# 03_OUTPUT.net
KiCad netlist of a schematic drawn in Altium Designer
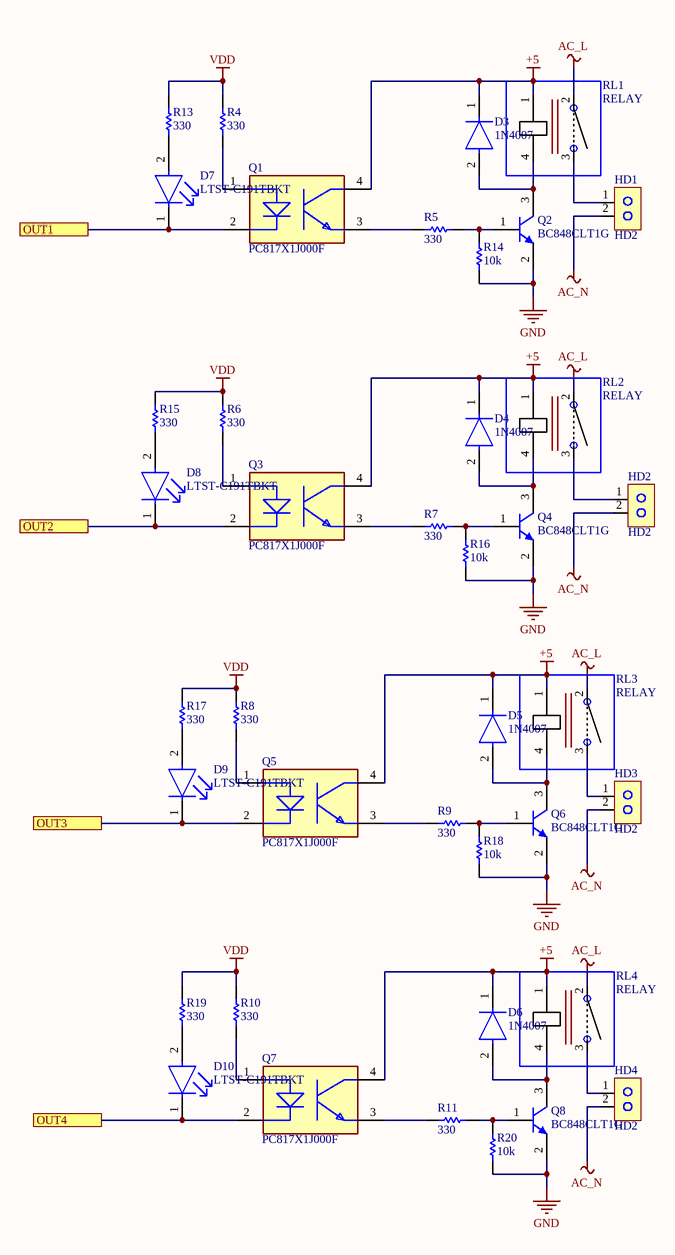
[diagram p0: 03. OUTPUT.SchDoc]

(export (version "E")
  (design (tool "Eeschema 10.0.6"))
  (components
    (comp (ref "D3")
      (value "1N4007")
      (footprint "FP-SMA-MFG")
      (description "DIODE GEN PURP 600V 1A SMA")
      (fields
        (field (name "MANUFACTURER") "STMicroelectronics")
        (field (name "OCTOPART") "https://octopart.com/stth1l06a-stmicroelectronics-324385")
      )
      (libsource (lib "Altium Content Vault") (part "d7152d700b627762746794eb795d46e"))
    )
    (comp (ref "D4")
      (value "1N4007")
      (footprint "FP-SMA-MFG")
      (description "DIODE GEN PURP 600V 1A SMA")
      (fields
        (field (name "MANUFACTURER") "STMicroelectronics")
        (field (name "OCTOPART") "https://octopart.com/stth1l06a-stmicroelectronics-324385")
      )
      (libsource (lib "Altium Content Vault") (part "d7152d700b627762746794eb795d46e"))
    )
    (comp (ref "D5")
      (value "1N4007")
      (footprint "FP-SMA-MFG")
      (description "DIODE GEN PURP 600V 1A SMA")
      (fields
        (field (name "MANUFACTURER") "STMicroelectronics")
        (field (name "OCTOPART") "https://octopart.com/stth1l06a-stmicroelectronics-324385")
      )
      (libsource (lib "Altium Content Vault") (part "d7152d700b627762746794eb795d46e"))
    )
    (comp (ref "D6")
      (value "1N4007")
      (footprint "FP-SMA-MFG")
      (description "DIODE GEN PURP 600V 1A SMA")
      (fields
        (field (name "MANUFACTURER") "STMicroelectronics")
        (field (name "OCTOPART") "https://octopart.com/stth1l06a-stmicroelectronics-324385")
      )
      (libsource (lib "Altium Content Vault") (part "d7152d700b627762746794eb795d46e"))
    )
    (comp (ref "D7")
      (value "LTST-C191TBKT")
      (footprint "FP-LTST-C191TBKT-MFG")
      (description "LED BLUE CLEAR CHIP SMD")
      (libsource (lib "Altium Content Vault") (part "8706943c75ba83719d021d2fdc84c58"))
    )
    (comp (ref "D8")
      (value "LTST-C191TBKT")
      (footprint "FP-LTST-C191TBKT-MFG")
      (description "LED BLUE CLEAR CHIP SMD")
      (libsource (lib "Altium Content Vault") (part "8706943c75ba83719d021d2fdc84c58"))
    )
    (comp (ref "D9")
      (value "LTST-C191TBKT")
      (footprint "FP-LTST-C191TBKT-MFG")
      (description "LED BLUE CLEAR CHIP SMD")
      (libsource (lib "Altium Content Vault") (part "8706943c75ba83719d021d2fdc84c58"))
    )
    (comp (ref "D10")
      (value "LTST-C191TBKT")
      (footprint "FP-LTST-C191TBKT-MFG")
      (description "LED BLUE CLEAR CHIP SMD")
      (libsource (lib "Altium Content Vault") (part "8706943c75ba83719d021d2fdc84c58"))
    )
    (comp (ref "HD1") (value "HD2") (footprint "HD2 5.08mm") (libsource (lib "SyTungNguyen") (part "HD2")))
    (comp (ref "HD2") (value "HD2") (footprint "HD2 5.08mm") (libsource (lib "SyTungNguyen") (part "HD2")))
    (comp (ref "HD3") (value "HD2") (footprint "HD2 5.08mm") (libsource (lib "SyTungNguyen") (part "HD2")))
    (comp (ref "HD4") (value "HD2") (footprint "HD2 5.08mm") (libsource (lib "SyTungNguyen") (part "HD2")))
    (comp (ref "Q1")
      (value "PC817X1J000F")
      (footprint "FP-PC817X1J000F-MFG")
      (description "OPTOISOLATOR 5KV TRANS 4DIP")
      (libsource (lib "Altium Content Vault") (part "8d9d817270a4e8f0d794346117f6aa3"))
    )
    (comp (ref "Q2")
      (value "BC848CLT1G")
      (footprint "SOT23-3")
      (description "General Purpose Transistor, NPN Silicon, 3-Pin SOT-23, Pb-Free, Tape and Reel")
      (fields (field (name "MANUFACTURER") "On Semiconductor"))
      (libsource (lib "SyTungNguyen") (part "ONSC-NPN-B1E2C3-3"))
    )
    (comp (ref "Q3")
      (value "PC817X1J000F")
      (footprint "FP-PC817X1J000F-MFG")
      (description "OPTOISOLATOR 5KV TRANS 4DIP")
      (libsource (lib "Altium Content Vault") (part "8d9d817270a4e8f0d794346117f6aa3"))
    )
    (comp (ref "Q4")
      (value "BC848CLT1G")
      (footprint "SOT23-3")
      (description "General Purpose Transistor, NPN Silicon, 3-Pin SOT-23, Pb-Free, Tape and Reel")
      (fields (field (name "MANUFACTURER") "On Semiconductor"))
      (libsource (lib "SyTungNguyen") (part "ONSC-NPN-B1E2C3-3"))
    )
    (comp (ref "Q5")
      (value "PC817X1J000F")
      (footprint "FP-PC817X1J000F-MFG")
      (description "OPTOISOLATOR 5KV TRANS 4DIP")
      (libsource (lib "Altium Content Vault") (part "8d9d817270a4e8f0d794346117f6aa3"))
    )
    (comp (ref "Q6")
      (value "BC848CLT1G")
      (footprint "SOT23-3")
      (description "General Purpose Transistor, NPN Silicon, 3-Pin SOT-23, Pb-Free, Tape and Reel")
      (fields (field (name "MANUFACTURER") "On Semiconductor"))
      (libsource (lib "SyTungNguyen") (part "ONSC-NPN-B1E2C3-3"))
    )
    (comp (ref "Q7")
      (value "PC817X1J000F")
      (footprint "FP-PC817X1J000F-MFG")
      (description "OPTOISOLATOR 5KV TRANS 4DIP")
      (libsource (lib "Altium Content Vault") (part "8d9d817270a4e8f0d794346117f6aa3"))
    )
    (comp (ref "Q8")
      (value "BC848CLT1G")
      (footprint "SOT23-3")
      (description "General Purpose Transistor, NPN Silicon, 3-Pin SOT-23, Pb-Free, Tape and Reel")
      (fields (field (name "MANUFACTURER") "On Semiconductor"))
      (libsource (lib "SyTungNguyen") (part "ONSC-NPN-B1E2C3-3"))
    )
    (comp (ref "R4")
      (value "330")
      (footprint "0603 RES")
      (fields (field (name "MANUFACTURER") "Vishay Dale") (field (name "PART NUMBER") "CRCW06030000Z0EB"))
      (libsource (lib "SyTungNguyen") (part "RES"))
    )
    (comp (ref "R5")
      (value "330")
      (footprint "0603 RES")
      (fields (field (name "MANUFACTURER") "Vishay Dale") (field (name "PART NUMBER") "CRCW06030000Z0EB"))
      (libsource (lib "SyTungNguyen") (part "RES"))
    )
    (comp (ref "R6")
      (value "330")
      (footprint "0603 RES")
      (fields (field (name "MANUFACTURER") "Vishay Dale") (field (name "PART NUMBER") "CRCW06030000Z0EB"))
      (libsource (lib "SyTungNguyen") (part "RES"))
    )
    (comp (ref "R7")
      (value "330")
      (footprint "0603 RES")
      (fields (field (name "MANUFACTURER") "Vishay Dale") (field (name "PART NUMBER") "CRCW06030000Z0EB"))
      (libsource (lib "SyTungNguyen") (part "RES"))
    )
    (comp (ref "R8")
      (value "330")
      (footprint "0603 RES")
      (fields (field (name "MANUFACTURER") "Vishay Dale") (field (name "PART NUMBER") "CRCW06030000Z0EB"))
      (libsource (lib "SyTungNguyen") (part "RES"))
    )
    (comp (ref "R9")
      (value "330")
      (footprint "0603 RES")
      (fields (field (name "MANUFACTURER") "Vishay Dale") (field (name "PART NUMBER") "CRCW06030000Z0EB"))
      (libsource (lib "SyTungNguyen") (part "RES"))
    )
    (comp (ref "R10")
      (value "330")
      (footprint "0603 RES")
      (fields (field (name "MANUFACTURER") "Vishay Dale") (field (name "PART NUMBER") "CRCW06030000Z0EB"))
      (libsource (lib "SyTungNguyen") (part "RES"))
    )
    (comp (ref "R11")
      (value "330")
      (footprint "0603 RES")
      (fields (field (name "MANUFACTURER") "Vishay Dale") (field (name "PART NUMBER") "CRCW06030000Z0EB"))
      (libsource (lib "SyTungNguyen") (part "RES"))
    )
    (comp (ref "R13")
      (value "330")
      (footprint "0603 RES")
      (fields (field (name "MANUFACTURER") "Vishay Dale") (field (name "PART NUMBER") "CRCW06030000Z0EB"))
      (libsource (lib "SyTungNguyen") (part "RES"))
    )
    (comp (ref "R14")
      (value "10k")
      (footprint "0603 RES")
      (fields (field (name "MANUFACTURER") "Vishay Dale") (field (name "PART NUMBER") "CRCW06030000Z0EB"))
      (libsource (lib "SyTungNguyen") (part "RES"))
    )
    (comp (ref "R15")
      (value "330")
      (footprint "0603 RES")
      (fields (field (name "MANUFACTURER") "Vishay Dale") (field (name "PART NUMBER") "CRCW06030000Z0EB"))
      (libsource (lib "SyTungNguyen") (part "RES"))
    )
    (comp (ref "R16")
      (value "10k")
      (footprint "0603 RES")
      (fields (field (name "MANUFACTURER") "Vishay Dale") (field (name "PART NUMBER") "CRCW06030000Z0EB"))
      (libsource (lib "SyTungNguyen") (part "RES"))
    )
    (comp (ref "R17")
      (value "330")
      (footprint "0603 RES")
      (fields (field (name "MANUFACTURER") "Vishay Dale") (field (name "PART NUMBER") "CRCW06030000Z0EB"))
      (libsource (lib "SyTungNguyen") (part "RES"))
    )
    (comp (ref "R18")
      (value "10k")
      (footprint "0603 RES")
      (fields (field (name "MANUFACTURER") "Vishay Dale") (field (name "PART NUMBER") "CRCW06030000Z0EB"))
      (libsource (lib "SyTungNguyen") (part "RES"))
    )
    (comp (ref "R19")
      (value "330")
      (footprint "0603 RES")
      (fields (field (name "MANUFACTURER") "Vishay Dale") (field (name "PART NUMBER") "CRCW06030000Z0EB"))
      (libsource (lib "SyTungNguyen") (part "RES"))
    )
    (comp (ref "R20")
      (value "10k")
      (footprint "0603 RES")
      (fields (field (name "MANUFACTURER") "Vishay Dale") (field (name "PART NUMBER") "CRCW06030000Z0EB"))
      (libsource (lib "SyTungNguyen") (part "RES"))
    )
    (comp (ref "RL1")
      (value "RELAY")
      (footprint "RELAY G5NB OMRON")
      (libsource (lib "SyTungNguyen") (part "RELAY 4PIN"))
    )
    (comp (ref "RL2")
      (value "RELAY")
      (footprint "RELAY G5NB OMRON")
      (libsource (lib "SyTungNguyen") (part "RELAY 4PIN"))
    )
    (comp (ref "RL3")
      (value "RELAY")
      (footprint "RELAY G5NB OMRON")
      (libsource (lib "SyTungNguyen") (part "RELAY 4PIN"))
    )
    (comp (ref "RL4")
      (value "RELAY")
      (footprint "RELAY G5NB OMRON")
      (libsource (lib "SyTungNguyen") (part "RELAY 4PIN"))
    )
  )
  (nets
    (net (code "1") (name "+5") (class "Default")
      (node (ref "D3") (pin "1") (pinfunction "C_1") (pintype "passive"))
      (node (ref "D4") (pin "1") (pinfunction "C_1") (pintype "passive"))
      (node (ref "D5") (pin "1") (pinfunction "C_1") (pintype "passive"))
      (node (ref "D6") (pin "1") (pinfunction "C_1") (pintype "passive"))
      (node (ref "Q1") (pin "4") (pinfunction "C_4") (pintype "passive"))
      (node (ref "Q3") (pin "4") (pinfunction "C_4") (pintype "passive"))
      (node (ref "Q5") (pin "4") (pinfunction "C_4") (pintype "passive"))
      (node (ref "Q7") (pin "4") (pinfunction "C_4") (pintype "passive"))
      (node (ref "RL1") (pin "1") (pinfunction "1_1") (pintype "passive"))
      (node (ref "RL2") (pin "1") (pinfunction "1_1") (pintype "passive"))
      (node (ref "RL3") (pin "1") (pinfunction "1_1") (pintype "passive"))
      (node (ref "RL4") (pin "1") (pinfunction "1_1") (pintype "passive"))
    )
    (net (code "2") (name "/OUT1") (class "Default")
      (node (ref "D7") (pin "1") (pinfunction "C_1") (pintype "passive"))
      (node (ref "Q1") (pin "2") (pinfunction "C_2") (pintype "passive"))
    )
    (net (code "3") (name "/OUT2") (class "Default")
      (node (ref "D8") (pin "1") (pinfunction "C_1") (pintype "passive"))
      (node (ref "Q3") (pin "2") (pinfunction "C_2") (pintype "passive"))
    )
    (net (code "4") (name "/OUT3") (class "Default")
      (node (ref "D9") (pin "1") (pinfunction "C_1") (pintype "passive"))
      (node (ref "Q5") (pin "2") (pinfunction "C_2") (pintype "passive"))
    )
    (net (code "5") (name "/OUT4") (class "Default")
      (node (ref "D10") (pin "1") (pinfunction "C_1") (pintype "passive"))
      (node (ref "Q7") (pin "2") (pinfunction "C_2") (pintype "passive"))
    )
    (net (code "6") (name "AC_L") (class "Default")
      (node (ref "RL1") (pin "2") (pinfunction "2_2") (pintype "passive"))
      (node (ref "RL2") (pin "2") (pinfunction "2_2") (pintype "passive"))
      (node (ref "RL3") (pin "2") (pinfunction "2_2") (pintype "passive"))
      (node (ref "RL4") (pin "2") (pinfunction "2_2") (pintype "passive"))
    )
    (net (code "7") (name "AC_N") (class "Default")
      (node (ref "HD1") (pin "2") (pinfunction "2_2") (pintype "passive"))
      (node (ref "HD2") (pin "2") (pinfunction "2_2") (pintype "passive"))
      (node (ref "HD3") (pin "2") (pinfunction "2_2") (pintype "passive"))
      (node (ref "HD4") (pin "2") (pinfunction "2_2") (pintype "passive"))
    )
    (net (code "8") (name "GND") (class "Default")
      (node (ref "Q2") (pin "2") (pinfunction "E_2") (pintype "passive"))
      (node (ref "Q4") (pin "2") (pinfunction "E_2") (pintype "passive"))
      (node (ref "Q6") (pin "2") (pinfunction "E_2") (pintype "passive"))
      (node (ref "Q8") (pin "2") (pinfunction "E_2") (pintype "passive"))
      (node (ref "R14") (pin "2") (pinfunction "2_2") (pintype "passive"))
      (node (ref "R16") (pin "2") (pinfunction "2_2") (pintype "passive"))
      (node (ref "R18") (pin "2") (pinfunction "2_2") (pintype "passive"))
      (node (ref "R20") (pin "2") (pinfunction "2_2") (pintype "passive"))
    )
    (net (code "9") (name "Net-(D3-A)") (class "Default")
      (node (ref "D3") (pin "2") (pinfunction "A_2") (pintype "passive"))
      (node (ref "Q2") (pin "3") (pinfunction "C_3") (pintype "passive"))
      (node (ref "RL1") (pin "4") (pinfunction "4_4") (pintype "passive"))
    )
    (net (code "10") (name "Net-(D4-A)") (class "Default")
      (node (ref "D4") (pin "2") (pinfunction "A_2") (pintype "passive"))
      (node (ref "Q4") (pin "3") (pinfunction "C_3") (pintype "passive"))
      (node (ref "RL2") (pin "4") (pinfunction "4_4") (pintype "passive"))
    )
    (net (code "11") (name "Net-(D5-A)") (class "Default")
      (node (ref "D5") (pin "2") (pinfunction "A_2") (pintype "passive"))
      (node (ref "Q6") (pin "3") (pinfunction "C_3") (pintype "passive"))
      (node (ref "RL3") (pin "4") (pinfunction "4_4") (pintype "passive"))
    )
    (net (code "12") (name "Net-(D6-A)") (class "Default")
      (node (ref "D6") (pin "2") (pinfunction "A_2") (pintype "passive"))
      (node (ref "Q8") (pin "3") (pinfunction "C_3") (pintype "passive"))
      (node (ref "RL4") (pin "4") (pinfunction "4_4") (pintype "passive"))
    )
    (net (code "13") (name "Net-(D7-A)") (class "Default")
      (node (ref "D7") (pin "2") (pinfunction "A_2") (pintype "passive"))
      (node (ref "R13") (pin "2") (pinfunction "2_2") (pintype "passive"))
    )
    (net (code "14") (name "Net-(D8-A)") (class "Default")
      (node (ref "D8") (pin "2") (pinfunction "A_2") (pintype "passive"))
      (node (ref "R15") (pin "2") (pinfunction "2_2") (pintype "passive"))
    )
    (net (code "15") (name "Net-(D9-A)") (class "Default")
      (node (ref "D9") (pin "2") (pinfunction "A_2") (pintype "passive"))
      (node (ref "R17") (pin "2") (pinfunction "2_2") (pintype "passive"))
    )
    (net (code "16") (name "Net-(D10-A)") (class "Default")
      (node (ref "D10") (pin "2") (pinfunction "A_2") (pintype "passive"))
      (node (ref "R19") (pin "2") (pinfunction "2_2") (pintype "passive"))
    )
    (net (code "17") (name "Net-(HD1-Pad1)") (class "Default")
      (node (ref "HD1") (pin "1") (pinfunction "1_1") (pintype "passive"))
      (node (ref "RL1") (pin "3") (pinfunction "3_3") (pintype "passive"))
    )
    (net (code "18") (name "Net-(HD2-Pad1)") (class "Default")
      (node (ref "HD2") (pin "1") (pinfunction "1_1") (pintype "passive"))
      (node (ref "RL2") (pin "3") (pinfunction "3_3") (pintype "passive"))
    )
    (net (code "19") (name "Net-(HD3-Pad1)") (class "Default")
      (node (ref "HD3") (pin "1") (pinfunction "1_1") (pintype "passive"))
      (node (ref "RL3") (pin "3") (pinfunction "3_3") (pintype "passive"))
    )
    (net (code "20") (name "Net-(HD4-Pad1)") (class "Default")
      (node (ref "HD4") (pin "1") (pinfunction "1_1") (pintype "passive"))
      (node (ref "RL4") (pin "3") (pinfunction "3_3") (pintype "passive"))
    )
    (net (code "21") (name "Net-(Q1-A)") (class "Default")
      (node (ref "Q1") (pin "1") (pinfunction "A_1") (pintype "passive"))
      (node (ref "R4") (pin "2") (pinfunction "2_2") (pintype "passive"))
    )
    (net (code "22") (name "Net-(Q1-E)") (class "Default")
      (node (ref "Q1") (pin "3") (pinfunction "E_3") (pintype "passive"))
      (node (ref "R5") (pin "2") (pinfunction "2_2") (pintype "passive"))
    )
    (net (code "23") (name "Net-(Q2-B)") (class "Default")
      (node (ref "Q2") (pin "1") (pinfunction "B_1") (pintype "passive"))
      (node (ref "R14") (pin "1") (pinfunction "1_1") (pintype "passive"))
      (node (ref "R5") (pin "1") (pinfunction "1_1") (pintype "passive"))
    )
    (net (code "24") (name "Net-(Q3-A)") (class "Default")
      (node (ref "Q3") (pin "1") (pinfunction "A_1") (pintype "passive"))
      (node (ref "R6") (pin "2") (pinfunction "2_2") (pintype "passive"))
    )
    (net (code "25") (name "Net-(Q3-E)") (class "Default")
      (node (ref "Q3") (pin "3") (pinfunction "E_3") (pintype "passive"))
      (node (ref "R7") (pin "2") (pinfunction "2_2") (pintype "passive"))
    )
    (net (code "26") (name "Net-(Q4-B)") (class "Default")
      (node (ref "Q4") (pin "1") (pinfunction "B_1") (pintype "passive"))
      (node (ref "R16") (pin "1") (pinfunction "1_1") (pintype "passive"))
      (node (ref "R7") (pin "1") (pinfunction "1_1") (pintype "passive"))
    )
    (net (code "27") (name "Net-(Q5-A)") (class "Default")
      (node (ref "Q5") (pin "1") (pinfunction "A_1") (pintype "passive"))
      (node (ref "R8") (pin "2") (pinfunction "2_2") (pintype "passive"))
    )
    (net (code "28") (name "Net-(Q5-E)") (class "Default")
      (node (ref "Q5") (pin "3") (pinfunction "E_3") (pintype "passive"))
      (node (ref "R9") (pin "2") (pinfunction "2_2") (pintype "passive"))
    )
    (net (code "29") (name "Net-(Q6-B)") (class "Default")
      (node (ref "Q6") (pin "1") (pinfunction "B_1") (pintype "passive"))
      (node (ref "R18") (pin "1") (pinfunction "1_1") (pintype "passive"))
      (node (ref "R9") (pin "1") (pinfunction "1_1") (pintype "passive"))
    )
    (net (code "30") (name "Net-(Q7-A)") (class "Default")
      (node (ref "Q7") (pin "1") (pinfunction "A_1") (pintype "passive"))
      (node (ref "R10") (pin "2") (pinfunction "2_2") (pintype "passive"))
    )
    (net (code "31") (name "Net-(Q7-E)") (class "Default")
      (node (ref "Q7") (pin "3") (pinfunction "E_3") (pintype "passive"))
      (node (ref "R11") (pin "2") (pinfunction "2_2") (pintype "passive"))
    )
    (net (code "32") (name "Net-(Q8-B)") (class "Default")
      (node (ref "Q8") (pin "1") (pinfunction "B_1") (pintype "passive"))
      (node (ref "R11") (pin "1") (pinfunction "1_1") (pintype "passive"))
      (node (ref "R20") (pin "1") (pinfunction "1_1") (pintype "passive"))
    )
    (net (code "33") (name "VDD") (class "Default")
      (node (ref "R10") (pin "1") (pinfunction "1_1") (pintype "passive"))
      (node (ref "R13") (pin "1") (pinfunction "1_1") (pintype "passive"))
      (node (ref "R15") (pin "1") (pinfunction "1_1") (pintype "passive"))
      (node (ref "R17") (pin "1") (pinfunction "1_1") (pintype "passive"))
      (node (ref "R19") (pin "1") (pinfunction "1_1") (pintype "passive"))
      (node (ref "R4") (pin "1") (pinfunction "1_1") (pintype "passive"))
      (node (ref "R6") (pin "1") (pinfunction "1_1") (pintype "passive"))
      (node (ref "R8") (pin "1") (pinfunction "1_1") (pintype "passive"))
    )
  )
)
